# esp32car.net
KiCad netlist of a schematic drawn in EasyEDA Pro
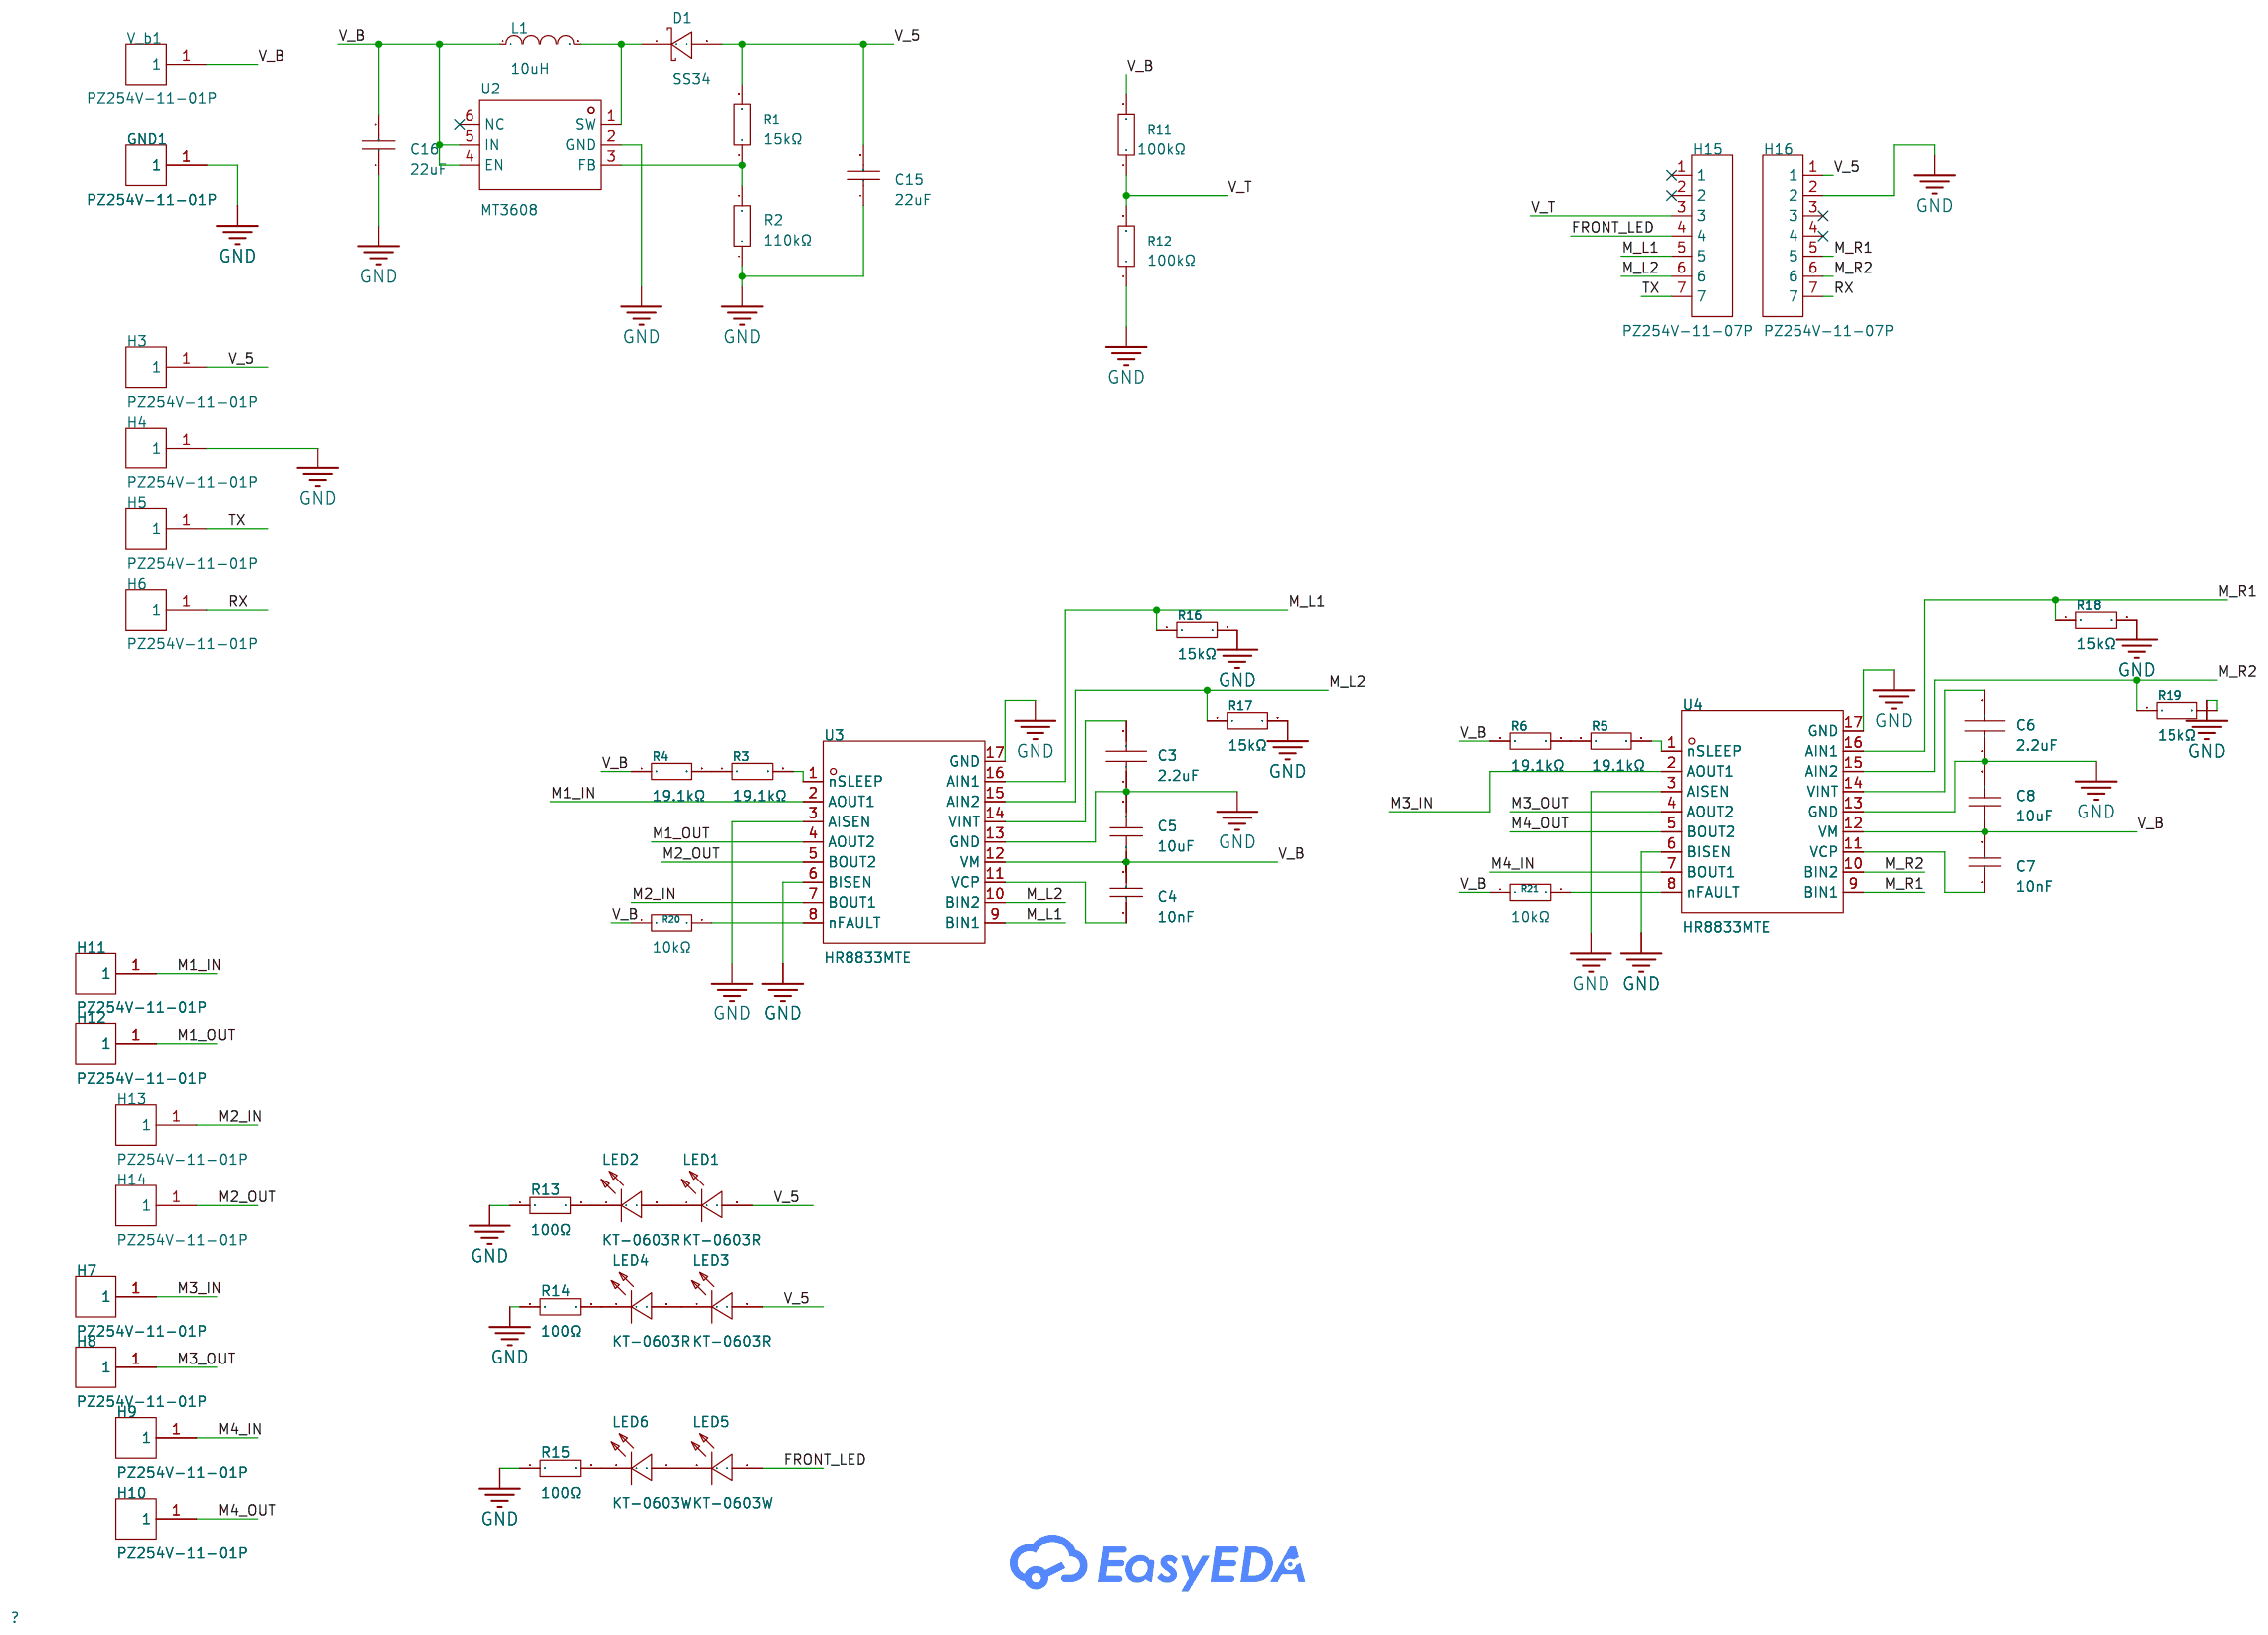
[diagram p0: schematic sheet]

(export (version "E")
  (design (tool "Eeschema 10.0.6"))
  (components
    (comp (ref "C3")
      (value "2.2uF")
      (footprint "easyedapro:C0402")
      (fields
        (field (name "Manufacturer Part") "CL05A225MQ5NSNC")
        (field (name "Manufacturer") "SAMSUNG(三星)")
      )
      (libsource (lib "easyedapro") (part "CL05A225MQ5NSNC"))
    )
    (comp (ref "C4")
      (value "10nF")
      (footprint "easyedapro:C0402")
      (fields
        (field (name "Manufacturer Part") "CL05B103KB5NNNC")
        (field (name "Manufacturer") "SAMSUNG(三星)")
      )
      (libsource (lib "easyedapro") (part "CL05B103KB5NNNC"))
    )
    (comp (ref "C5")
      (value "10uF")
      (footprint "easyedapro:C0603")
      (fields
        (field (name "Manufacturer Part") "CL10A106KP8NNNC")
        (field (name "Manufacturer") "SAMSUNG(三星)")
      )
      (libsource (lib "easyedapro") (part "CL10A106KP8NNNC"))
    )
    (comp (ref "C6")
      (value "2.2uF")
      (footprint "easyedapro:C0402")
      (fields
        (field (name "Manufacturer Part") "CL05A225MQ5NSNC")
        (field (name "Manufacturer") "SAMSUNG(三星)")
      )
      (libsource (lib "easyedapro") (part "CL05A225MQ5NSNC"))
    )
    (comp (ref "C7")
      (value "10nF")
      (footprint "easyedapro:C0402")
      (fields
        (field (name "Manufacturer Part") "CL05B103KB5NNNC")
        (field (name "Manufacturer") "SAMSUNG(三星)")
      )
      (libsource (lib "easyedapro") (part "CL05B103KB5NNNC"))
    )
    (comp (ref "C8")
      (value "10uF")
      (footprint "easyedapro:C0603")
      (fields
        (field (name "Manufacturer Part") "CL10A106KP8NNNC")
        (field (name "Manufacturer") "SAMSUNG(三星)")
      )
      (libsource (lib "easyedapro") (part "CL10A106KP8NNNC"))
    )
    (comp (ref "C15")
      (value "22uF")
      (footprint "easyedapro:C1206")
      (description "Capacitance:22uF Tolerance:±10% Tolerance:±10% Voltage Rating:10V Temperature Coefficient:X5R")
      (fields (field (name "Manufacturer Part") "1206X226K100NT") (field (name "Manufacturer") "FH(风华)"))
      (libsource (lib "easyedapro") (part "1206X226K100NT"))
    )
    (comp (ref "C16")
      (value "22uF")
      (footprint "easyedapro:C1206")
      (description "Capacitance:22uF Tolerance:±10% Tolerance:±10% Voltage Rating:10V Temperature Coefficient:X5R")
      (fields (field (name "Manufacturer Part") "1206X226K100NT") (field (name "Manufacturer") "FH(风华)"))
      (libsource (lib "easyedapro") (part "1206X226K100NT"))
    )
    (comp (ref "D1")
      (value "SS34")
      (footprint "easyedapro:SMA_L4.3-W2.6-LS5.2-RD")
      (fields (field (name "Manufacturer") "MDD(辰达半导体)"))
      (libsource (lib "easyedapro") (part "SS34_C8678"))
    )
    (comp (ref "GND1")
      (value "PZ254V-11-01P")
      (footprint "easyedapro:HDR-TH_1P-P2.54-V-M")
      (fields (field (name "Manufacturer") "XFCN(兴飞)"))
      (libsource (lib "easyedapro") (part "PZ254V-11-01P"))
    )
    (comp (ref "H3")
      (value "PZ254V-11-01P")
      (footprint "easyedapro:HDR-TH_1P-P2.54-V-M")
      (fields (field (name "Manufacturer") "XFCN(兴飞)"))
      (libsource (lib "easyedapro") (part "PZ254V-11-01P"))
    )
    (comp (ref "H4")
      (value "PZ254V-11-01P")
      (footprint "easyedapro:HDR-TH_1P-P2.54-V-M")
      (fields (field (name "Manufacturer") "XFCN(兴飞)"))
      (libsource (lib "easyedapro") (part "PZ254V-11-01P"))
    )
    (comp (ref "H5")
      (value "PZ254V-11-01P")
      (footprint "easyedapro:HDR-TH_1P-P2.54-V-M")
      (fields (field (name "Manufacturer") "XFCN(兴飞)"))
      (libsource (lib "easyedapro") (part "PZ254V-11-01P"))
    )
    (comp (ref "H6")
      (value "PZ254V-11-01P")
      (footprint "easyedapro:HDR-TH_1P-P2.54-V-M")
      (fields (field (name "Manufacturer") "XFCN(兴飞)"))
      (libsource (lib "easyedapro") (part "PZ254V-11-01P"))
    )
    (comp (ref "H7")
      (value "PZ254V-11-01P")
      (footprint "easyedapro:HDR-TH_1P-P2.54-V-M")
      (fields (field (name "Manufacturer") "XFCN(兴飞)"))
      (libsource (lib "easyedapro") (part "PZ254V-11-01P"))
    )
    (comp (ref "H8")
      (value "PZ254V-11-01P")
      (footprint "easyedapro:HDR-TH_1P-P2.54-V-M")
      (fields (field (name "Manufacturer") "XFCN(兴飞)"))
      (libsource (lib "easyedapro") (part "PZ254V-11-01P"))
    )
    (comp (ref "H9")
      (value "PZ254V-11-01P")
      (footprint "easyedapro:HDR-TH_1P-P2.54-V-M")
      (fields (field (name "Manufacturer") "XFCN(兴飞)"))
      (libsource (lib "easyedapro") (part "PZ254V-11-01P"))
    )
    (comp (ref "H10")
      (value "PZ254V-11-01P")
      (footprint "easyedapro:HDR-TH_1P-P2.54-V-M")
      (fields (field (name "Manufacturer") "XFCN(兴飞)"))
      (libsource (lib "easyedapro") (part "PZ254V-11-01P"))
    )
    (comp (ref "H11")
      (value "PZ254V-11-01P")
      (footprint "easyedapro:HDR-TH_1P-P2.54-V-M")
      (fields (field (name "Manufacturer") "XFCN(兴飞)"))
      (libsource (lib "easyedapro") (part "PZ254V-11-01P"))
    )
    (comp (ref "H12")
      (value "PZ254V-11-01P")
      (footprint "easyedapro:HDR-TH_1P-P2.54-V-M")
      (fields (field (name "Manufacturer") "XFCN(兴飞)"))
      (libsource (lib "easyedapro") (part "PZ254V-11-01P"))
    )
    (comp (ref "H13")
      (value "PZ254V-11-01P")
      (footprint "easyedapro:HDR-TH_1P-P2.54-V-M")
      (fields (field (name "Manufacturer") "XFCN(兴飞)"))
      (libsource (lib "easyedapro") (part "PZ254V-11-01P"))
    )
    (comp (ref "H14")
      (value "PZ254V-11-01P")
      (footprint "easyedapro:HDR-TH_1P-P2.54-V-M")
      (fields (field (name "Manufacturer") "XFCN(兴飞)"))
      (libsource (lib "easyedapro") (part "PZ254V-11-01P"))
    )
    (comp (ref "H15")
      (value "PZ254V-11-07P")
      (footprint "easyedapro:HDR-TH_7P-P2.54-V-M")
      (fields (field (name "Manufacturer") "XFCN(兴飞)"))
      (libsource (lib "easyedapro") (part "PZ254V-11-07P"))
    )
    (comp (ref "H16")
      (value "PZ254V-11-07P")
      (footprint "easyedapro:HDR-TH_7P-P2.54-V-M")
      (fields (field (name "Manufacturer") "XFCN(兴飞)"))
      (libsource (lib "easyedapro") (part "PZ254V-11-07P"))
    )
    (comp (ref "L1")
      (value "10uH")
      (footprint "easyedapro:L1008")
      (fields (field (name "Manufacturer Part") "MLP2520S100MT0S1") (field (name "Manufacturer") "TDK"))
      (libsource (lib "easyedapro") (part "MLP2520S100MT0S1"))
    )
    (comp (ref "LED1")
      (value "KT-0603R")
      (footprint "easyedapro:LED0603-RD")
      (fields (field (name "Manufacturer") "KENTO"))
      (libsource (lib "easyedapro") (part "KT-0603R"))
    )
    (comp (ref "LED2")
      (value "KT-0603R")
      (footprint "easyedapro:LED0603-RD")
      (fields (field (name "Manufacturer") "KENTO"))
      (libsource (lib "easyedapro") (part "KT-0603R"))
    )
    (comp (ref "LED3")
      (value "KT-0603R")
      (footprint "easyedapro:LED0603-RD")
      (fields (field (name "Manufacturer") "KENTO"))
      (libsource (lib "easyedapro") (part "KT-0603R"))
    )
    (comp (ref "LED4")
      (value "KT-0603R")
      (footprint "easyedapro:LED0603-RD")
      (fields (field (name "Manufacturer") "KENTO"))
      (libsource (lib "easyedapro") (part "KT-0603R"))
    )
    (comp (ref "LED5")
      (value "KT-0603W")
      (footprint "easyedapro:LED0603-R-RD_WHITE")
      (description "Emitted Color:White")
      (fields (field (name "Manufacturer") "KENTO"))
      (libsource (lib "easyedapro") (part "0603White light_C2290"))
    )
    (comp (ref "LED6")
      (value "KT-0603W")
      (footprint "easyedapro:LED0603-R-RD_WHITE")
      (description "Emitted Color:White")
      (fields (field (name "Manufacturer") "KENTO"))
      (libsource (lib "easyedapro") (part "0603White light_C2290"))
    )
    (comp (ref "R1")
      (value "15kΩ")
      (footprint "easyedapro:R0402")
      (fields
        (field (name "Manufacturer Part") "0402WGF1502TCE")
        (field (name "Manufacturer") "UNI-ROYAL(厚声)")
      )
      (libsource (lib "easyedapro") (part "0402WGF1502TCE"))
    )
    (comp (ref "R2")
      (value "110kΩ")
      (footprint "easyedapro:R0603")
      (fields
        (field (name "Manufacturer Part") "0603WAF1103T5E")
        (field (name "Manufacturer") "UNI-ROYAL(厚声)")
      )
      (libsource (lib "easyedapro") (part "0603WAF1103T5E"))
    )
    (comp (ref "R3")
      (value "19.1kΩ")
      (footprint "easyedapro:R0402")
      (fields
        (field (name "Manufacturer Part") "0402WGF1912TCE")
        (field (name "Manufacturer") "UNI-ROYAL(厚声)")
      )
      (libsource (lib "easyedapro") (part "0402WGF1912TCE"))
    )
    (comp (ref "R4")
      (value "19.1kΩ")
      (footprint "easyedapro:R0402")
      (fields
        (field (name "Manufacturer Part") "0402WGF1912TCE")
        (field (name "Manufacturer") "UNI-ROYAL(厚声)")
      )
      (libsource (lib "easyedapro") (part "0402WGF1912TCE"))
    )
    (comp (ref "R5")
      (value "19.1kΩ")
      (footprint "easyedapro:R0402")
      (fields
        (field (name "Manufacturer Part") "0402WGF1912TCE")
        (field (name "Manufacturer") "UNI-ROYAL(厚声)")
      )
      (libsource (lib "easyedapro") (part "0402WGF1912TCE"))
    )
    (comp (ref "R6")
      (value "19.1kΩ")
      (footprint "easyedapro:R0402")
      (fields
        (field (name "Manufacturer Part") "0402WGF1912TCE")
        (field (name "Manufacturer") "UNI-ROYAL(厚声)")
      )
      (libsource (lib "easyedapro") (part "0402WGF1912TCE"))
    )
    (comp (ref "R11")
      (value "100kΩ")
      (footprint "easyedapro:R0402")
      (fields
        (field (name "Manufacturer Part") "0402WGF1003TCE")
        (field (name "Manufacturer") "UNI-ROYAL(厚声)")
      )
      (libsource (lib "easyedapro") (part "0402WGF1003TCE"))
    )
    (comp (ref "R12")
      (value "100kΩ")
      (footprint "easyedapro:R0402")
      (fields
        (field (name "Manufacturer Part") "0402WGF1003TCE")
        (field (name "Manufacturer") "UNI-ROYAL(厚声)")
      )
      (libsource (lib "easyedapro") (part "0402WGF1003TCE"))
    )
    (comp (ref "R13")
      (value "100Ω")
      (footprint "easyedapro:R0402")
      (fields
        (field (name "Manufacturer Part") "0402WGF1000TCE")
        (field (name "Manufacturer") "UNI-ROYAL(厚声)")
      )
      (libsource (lib "easyedapro") (part "0402WGF1000TCE"))
    )
    (comp (ref "R14")
      (value "100Ω")
      (footprint "easyedapro:R0402")
      (fields
        (field (name "Manufacturer Part") "0402WGF1000TCE")
        (field (name "Manufacturer") "UNI-ROYAL(厚声)")
      )
      (libsource (lib "easyedapro") (part "0402WGF1000TCE"))
    )
    (comp (ref "R15")
      (value "100Ω")
      (footprint "easyedapro:R0402")
      (fields
        (field (name "Manufacturer Part") "0402WGF1000TCE")
        (field (name "Manufacturer") "UNI-ROYAL(厚声)")
      )
      (libsource (lib "easyedapro") (part "0402WGF1000TCE"))
    )
    (comp (ref "R16")
      (value "15kΩ")
      (footprint "easyedapro:R0402")
      (fields
        (field (name "Manufacturer Part") "0402WGF1502TCE")
        (field (name "Manufacturer") "UNI-ROYAL(厚声)")
      )
      (libsource (lib "easyedapro") (part "0402WGF1502TCE"))
    )
    (comp (ref "R17")
      (value "15kΩ")
      (footprint "easyedapro:R0402")
      (fields
        (field (name "Manufacturer Part") "0402WGF1502TCE")
        (field (name "Manufacturer") "UNI-ROYAL(厚声)")
      )
      (libsource (lib "easyedapro") (part "0402WGF1502TCE"))
    )
    (comp (ref "R18")
      (value "15kΩ")
      (footprint "easyedapro:R0402")
      (fields
        (field (name "Manufacturer Part") "0402WGF1502TCE")
        (field (name "Manufacturer") "UNI-ROYAL(厚声)")
      )
      (libsource (lib "easyedapro") (part "0402WGF1502TCE"))
    )
    (comp (ref "R19")
      (value "15kΩ")
      (footprint "easyedapro:R0402")
      (fields
        (field (name "Manufacturer Part") "0402WGF1502TCE")
        (field (name "Manufacturer") "UNI-ROYAL(厚声)")
      )
      (libsource (lib "easyedapro") (part "0402WGF1502TCE"))
    )
    (comp (ref "R20")
      (value "10kΩ")
      (footprint "easyedapro:R0603")
      (fields
        (field (name "Manufacturer Part") "0603WAF1002T5E")
        (field (name "Manufacturer") "UNI-ROYAL(厚声)")
      )
      (libsource (lib "easyedapro") (part "0603WAF1002T5E"))
    )
    (comp (ref "R21")
      (value "10kΩ")
      (footprint "easyedapro:R0603")
      (fields
        (field (name "Manufacturer Part") "0603WAF1002T5E")
        (field (name "Manufacturer") "UNI-ROYAL(厚声)")
      )
      (libsource (lib "easyedapro") (part "0603WAF1002T5E"))
    )
    (comp (ref "U2")
      (value "MT3608")
      (footprint "easyedapro:SOT-23-6_L2.9-W1.6-P0.95-LS2.8-BL")
      (fields (field (name "Manufacturer") "西安航天民芯"))
      (libsource (lib "easyedapro") (part "MT3608"))
    )
    (comp (ref "U3")
      (value "HR8833MTE")
      (footprint "easyedapro:TSSOP-16_L5.0-W4.4-P0.65-LS6.4-BL-EP3.0")
      (fields (field (name "Manufacturer") "嘉兴禾润"))
      (libsource (lib "easyedapro") (part "HR8833MTE"))
    )
    (comp (ref "U4")
      (value "HR8833MTE")
      (footprint "easyedapro:TSSOP-16_L5.0-W4.4-P0.65-LS6.4-BL-EP3.0")
      (fields (field (name "Manufacturer") "嘉兴禾润"))
      (libsource (lib "easyedapro") (part "HR8833MTE"))
    )
    (comp (ref "V_b1")
      (value "PZ254V-11-01P")
      (footprint "easyedapro:HDR-TH_1P-P2.54-V-M")
      (fields (field (name "Manufacturer") "XFCN(兴飞)"))
      (libsource (lib "easyedapro") (part "PZ254V-11-01P"))
    )
  )
  (nets
    (net (code "1") (name "/FRONT_LED") (class "Default")
      (node (ref "H15") (pin "4") (pinfunction "4_4") (pintype "unspecified"))
      (node (ref "LED5") (pin "1") (pinfunction "A_1") (pintype "unspecified"))
    )
    (net (code "2") (name "/M1_IN") (class "Default")
      (node (ref "H11") (pin "1") (pinfunction "1_1") (pintype "unspecified"))
      (node (ref "U3") (pin "2") (pinfunction "AOUT1_2") (pintype "unspecified"))
    )
    (net (code "3") (name "/M1_OUT") (class "Default")
      (node (ref "H12") (pin "1") (pinfunction "1_1") (pintype "unspecified"))
      (node (ref "U3") (pin "4") (pinfunction "AOUT2_4") (pintype "unspecified"))
    )
    (net (code "4") (name "/M2_IN") (class "Default")
      (node (ref "H13") (pin "1") (pinfunction "1_1") (pintype "unspecified"))
      (node (ref "U3") (pin "7") (pinfunction "BOUT1_7") (pintype "unspecified"))
    )
    (net (code "5") (name "/M2_OUT") (class "Default")
      (node (ref "H14") (pin "1") (pinfunction "1_1") (pintype "unspecified"))
      (node (ref "U3") (pin "5") (pinfunction "BOUT2_5") (pintype "unspecified"))
    )
    (net (code "6") (name "/M3_IN") (class "Default")
      (node (ref "H7") (pin "1") (pinfunction "1_1") (pintype "unspecified"))
      (node (ref "U4") (pin "2") (pinfunction "AOUT1_2") (pintype "unspecified"))
    )
    (net (code "7") (name "/M3_OUT") (class "Default")
      (node (ref "H8") (pin "1") (pinfunction "1_1") (pintype "unspecified"))
      (node (ref "U4") (pin "4") (pinfunction "AOUT2_4") (pintype "unspecified"))
    )
    (net (code "8") (name "/M4_IN") (class "Default")
      (node (ref "H9") (pin "1") (pinfunction "1_1") (pintype "unspecified"))
      (node (ref "U4") (pin "7") (pinfunction "BOUT1_7") (pintype "unspecified"))
    )
    (net (code "9") (name "/M4_OUT") (class "Default")
      (node (ref "H10") (pin "1") (pinfunction "1_1") (pintype "unspecified"))
      (node (ref "U4") (pin "5") (pinfunction "BOUT2_5") (pintype "unspecified"))
    )
    (net (code "10") (name "/M_L1") (class "Default")
      (node (ref "H15") (pin "5") (pinfunction "5_5") (pintype "unspecified"))
      (node (ref "R16") (pin "1") (pinfunction "1_1") (pintype "input"))
      (node (ref "U3") (pin "16") (pinfunction "AIN1_16") (pintype "unspecified"))
      (node (ref "U3") (pin "9") (pinfunction "BIN1_9") (pintype "unspecified"))
    )
    (net (code "11") (name "/M_L2") (class "Default")
      (node (ref "H15") (pin "6") (pinfunction "6_6") (pintype "unspecified"))
      (node (ref "R17") (pin "1") (pinfunction "1_1") (pintype "input"))
      (node (ref "U3") (pin "10") (pinfunction "BIN2_10") (pintype "unspecified"))
      (node (ref "U3") (pin "15") (pinfunction "AIN2_15") (pintype "unspecified"))
    )
    (net (code "12") (name "/M_R1") (class "Default")
      (node (ref "H16") (pin "5") (pinfunction "5_5") (pintype "unspecified"))
      (node (ref "R18") (pin "1") (pinfunction "1_1") (pintype "input"))
      (node (ref "U4") (pin "16") (pinfunction "AIN1_16") (pintype "unspecified"))
      (node (ref "U4") (pin "9") (pinfunction "BIN1_9") (pintype "unspecified"))
    )
    (net (code "13") (name "/M_R2") (class "Default")
      (node (ref "H16") (pin "6") (pinfunction "6_6") (pintype "unspecified"))
      (node (ref "R19") (pin "1") (pinfunction "1_1") (pintype "input"))
      (node (ref "U4") (pin "10") (pinfunction "BIN2_10") (pintype "unspecified"))
      (node (ref "U4") (pin "15") (pinfunction "AIN2_15") (pintype "unspecified"))
    )
    (net (code "14") (name "/RX") (class "Default")
      (node (ref "H16") (pin "7") (pinfunction "7_7") (pintype "unspecified"))
      (node (ref "H6") (pin "1") (pinfunction "1_1") (pintype "unspecified"))
    )
    (net (code "15") (name "/TX") (class "Default")
      (node (ref "H15") (pin "7") (pinfunction "7_7") (pintype "unspecified"))
      (node (ref "H5") (pin "1") (pinfunction "1_1") (pintype "unspecified"))
    )
    (net (code "16") (name "/V_5") (class "Default")
      (node (ref "C15") (pin "2") (pinfunction "2_2") (pintype "input"))
      (node (ref "D1") (pin "2") (pinfunction "A_2") (pintype "unspecified"))
      (node (ref "H16") (pin "1") (pinfunction "1_1") (pintype "unspecified"))
      (node (ref "H3") (pin "1") (pinfunction "1_1") (pintype "unspecified"))
      (node (ref "LED1") (pin "2") (pinfunction "A_2") (pintype "unspecified"))
      (node (ref "LED3") (pin "2") (pinfunction "A_2") (pintype "unspecified"))
      (node (ref "R1") (pin "2") (pinfunction "2_2") (pintype "input"))
    )
    (net (code "17") (name "/V_B") (class "Default")
      (node (ref "C16") (pin "2") (pinfunction "2_2") (pintype "input"))
      (node (ref "C4") (pin "2") (pinfunction "2_2") (pintype "input"))
      (node (ref "C5") (pin "1") (pinfunction "1_1") (pintype "unspecified"))
      (node (ref "C7") (pin "2") (pinfunction "2_2") (pintype "input"))
      (node (ref "C8") (pin "1") (pinfunction "1_1") (pintype "unspecified"))
      (node (ref "L1") (pin "1") (pinfunction "1_1") (pintype "unspecified"))
      (node (ref "R11") (pin "2") (pinfunction "2_2") (pintype "input"))
      (node (ref "R20") (pin "1") (pinfunction "1_1") (pintype "input"))
      (node (ref "R21") (pin "1") (pinfunction "1_1") (pintype "input"))
      (node (ref "R4") (pin "1") (pinfunction "1_1") (pintype "input"))
      (node (ref "R6") (pin "1") (pinfunction "1_1") (pintype "input"))
      (node (ref "U2") (pin "4") (pinfunction "EN_4") (pintype "unspecified"))
      (node (ref "U2") (pin "5") (pinfunction "IN_5") (pintype "unspecified"))
      (node (ref "U3") (pin "12") (pinfunction "VM_12") (pintype "unspecified"))
      (node (ref "U4") (pin "12") (pinfunction "VM_12") (pintype "unspecified"))
      (node (ref "V_b1") (pin "1") (pinfunction "1_1") (pintype "unspecified"))
    )
    (net (code "18") (name "/V_T") (class "Default")
      (node (ref "H15") (pin "3") (pinfunction "3_3") (pintype "unspecified"))
      (node (ref "R11") (pin "1") (pinfunction "1_1") (pintype "input"))
      (node (ref "R12") (pin "2") (pinfunction "2_2") (pintype "input"))
    )
    (net (code "19") (name "GND") (class "Default")
      (node (ref "C15") (pin "1") (pinfunction "1_1") (pintype "input"))
      (node (ref "C16") (pin "1") (pinfunction "1_1") (pintype "input"))
      (node (ref "C3") (pin "1") (pinfunction "1_1") (pintype "unspecified"))
      (node (ref "C5") (pin "2") (pinfunction "2_2") (pintype "unspecified"))
      (node (ref "C6") (pin "1") (pinfunction "1_1") (pintype "unspecified"))
      (node (ref "C8") (pin "2") (pinfunction "2_2") (pintype "unspecified"))
      (node (ref "GND1") (pin "1") (pinfunction "1_1") (pintype "unspecified"))
      (node (ref "H16") (pin "2") (pinfunction "2_2") (pintype "unspecified"))
      (node (ref "H4") (pin "1") (pinfunction "1_1") (pintype "unspecified"))
      (node (ref "R12") (pin "1") (pinfunction "1_1") (pintype "input"))
      (node (ref "R13") (pin "1") (pinfunction "1_1") (pintype "input"))
      (node (ref "R14") (pin "1") (pinfunction "1_1") (pintype "input"))
      (node (ref "R15") (pin "1") (pinfunction "1_1") (pintype "input"))
      (node (ref "R16") (pin "2") (pinfunction "2_2") (pintype "input"))
      (node (ref "R17") (pin "2") (pinfunction "2_2") (pintype "input"))
      (node (ref "R18") (pin "2") (pinfunction "2_2") (pintype "input"))
      (node (ref "R19") (pin "2") (pinfunction "2_2") (pintype "input"))
      (node (ref "R2") (pin "1") (pinfunction "1_1") (pintype "input"))
      (node (ref "U2") (pin "2") (pinfunction "GND_2") (pintype "unspecified"))
      (node (ref "U3") (pin "13") (pinfunction "GND_13") (pintype "unspecified"))
      (node (ref "U3") (pin "17") (pinfunction "GND_17") (pintype "unspecified"))
      (node (ref "U3") (pin "3") (pinfunction "AISEN_3") (pintype "unspecified"))
      (node (ref "U3") (pin "6") (pinfunction "BISEN_6") (pintype "unspecified"))
      (node (ref "U4") (pin "13") (pinfunction "GND_13") (pintype "unspecified"))
      (node (ref "U4") (pin "17") (pinfunction "GND_17") (pintype "unspecified"))
      (node (ref "U4") (pin "3") (pinfunction "AISEN_3") (pintype "unspecified"))
      (node (ref "U4") (pin "6") (pinfunction "BISEN_6") (pintype "unspecified"))
    )
    (net (code "20") (name "Net-(D1-K)") (class "Default")
      (node (ref "D1") (pin "1") (pinfunction "K_1") (pintype "unspecified"))
      (node (ref "L1") (pin "2") (pinfunction "2_2") (pintype "unspecified"))
      (node (ref "U2") (pin "1") (pinfunction "SW_1") (pintype "unspecified"))
    )
    (net (code "21") (name "Net-(LED1-K)") (class "Default")
      (node (ref "LED1") (pin "1") (pinfunction "K_1") (pintype "unspecified"))
      (node (ref "LED2") (pin "2") (pinfunction "A_2") (pintype "unspecified"))
    )
    (net (code "22") (name "Net-(LED2-K)") (class "Default")
      (node (ref "LED2") (pin "1") (pinfunction "K_1") (pintype "unspecified"))
      (node (ref "R13") (pin "2") (pinfunction "2_2") (pintype "input"))
    )
    (net (code "23") (name "Net-(LED3-K)") (class "Default")
      (node (ref "LED3") (pin "1") (pinfunction "K_1") (pintype "unspecified"))
      (node (ref "LED4") (pin "2") (pinfunction "A_2") (pintype "unspecified"))
    )
    (net (code "24") (name "Net-(LED4-K)") (class "Default")
      (node (ref "LED4") (pin "1") (pinfunction "K_1") (pintype "unspecified"))
      (node (ref "R14") (pin "2") (pinfunction "2_2") (pintype "input"))
    )
    (net (code "25") (name "Net-(LED5-K)") (class "Default")
      (node (ref "LED5") (pin "2") (pinfunction "K_2") (pintype "unspecified"))
      (node (ref "LED6") (pin "1") (pinfunction "A_1") (pintype "unspecified"))
    )
    (net (code "26") (name "Net-(LED6-K)") (class "Default")
      (node (ref "LED6") (pin "2") (pinfunction "K_2") (pintype "unspecified"))
      (node (ref "R15") (pin "2") (pinfunction "2_2") (pintype "input"))
    )
    (net (code "27") (name "Net-(R3-Pad1)") (class "Default")
      (node (ref "R3") (pin "1") (pinfunction "1_1") (pintype "input"))
      (node (ref "R4") (pin "2") (pinfunction "2_2") (pintype "input"))
    )
    (net (code "28") (name "Net-(R5-Pad1)") (class "Default")
      (node (ref "R5") (pin "1") (pinfunction "1_1") (pintype "input"))
      (node (ref "R6") (pin "2") (pinfunction "2_2") (pintype "input"))
    )
    (net (code "29") (name "Net-(U2-FB)") (class "Default")
      (node (ref "R1") (pin "1") (pinfunction "1_1") (pintype "input"))
      (node (ref "R2") (pin "2") (pinfunction "2_2") (pintype "input"))
      (node (ref "U2") (pin "3") (pinfunction "FB_3") (pintype "unspecified"))
    )
    (net (code "30") (name "Net-(U3-VCP)") (class "Default")
      (node (ref "C4") (pin "1") (pinfunction "1_1") (pintype "input"))
      (node (ref "U3") (pin "11") (pinfunction "VCP_11") (pintype "unspecified"))
    )
    (net (code "31") (name "Net-(U3-VINT)") (class "Default")
      (node (ref "C3") (pin "2") (pinfunction "2_2") (pintype "unspecified"))
      (node (ref "U3") (pin "14") (pinfunction "VINT_14") (pintype "unspecified"))
    )
    (net (code "32") (name "Net-(U3-nFAULT)") (class "Default")
      (node (ref "R20") (pin "2") (pinfunction "2_2") (pintype "input"))
      (node (ref "U3") (pin "8") (pinfunction "nFAULT_8") (pintype "unspecified"))
    )
    (net (code "33") (name "Net-(U3-nSLEEP)") (class "Default")
      (node (ref "R3") (pin "2") (pinfunction "2_2") (pintype "input"))
      (node (ref "U3") (pin "1") (pinfunction "nSLEEP_1") (pintype "unspecified"))
    )
    (net (code "34") (name "Net-(U4-VCP)") (class "Default")
      (node (ref "C7") (pin "1") (pinfunction "1_1") (pintype "input"))
      (node (ref "U4") (pin "11") (pinfunction "VCP_11") (pintype "unspecified"))
    )
    (net (code "35") (name "Net-(U4-VINT)") (class "Default")
      (node (ref "C6") (pin "2") (pinfunction "2_2") (pintype "unspecified"))
      (node (ref "U4") (pin "14") (pinfunction "VINT_14") (pintype "unspecified"))
    )
    (net (code "36") (name "Net-(U4-nFAULT)") (class "Default")
      (node (ref "R21") (pin "2") (pinfunction "2_2") (pintype "input"))
      (node (ref "U4") (pin "8") (pinfunction "nFAULT_8") (pintype "unspecified"))
    )
    (net (code "37") (name "Net-(U4-nSLEEP)") (class "Default")
      (node (ref "R5") (pin "2") (pinfunction "2_2") (pintype "input"))
      (node (ref "U4") (pin "1") (pinfunction "nSLEEP_1") (pintype "unspecified"))
    )
    (net (code "38") (name "unconnected-(H15-Pad1)") (class "Default")
      (node (ref "H15") (pin "1") (pinfunction "1_1") (pintype "unspecified+no_connect"))
    )
    (net (code "39") (name "unconnected-(H15-Pad2)") (class "Default")
      (node (ref "H15") (pin "2") (pinfunction "2_2") (pintype "unspecified+no_connect"))
    )
    (net (code "40") (name "unconnected-(H16-Pad3)") (class "Default")
      (node (ref "H16") (pin "3") (pinfunction "3_3") (pintype "unspecified+no_connect"))
    )
    (net (code "41") (name "unconnected-(H16-Pad4)") (class "Default")
      (node (ref "H16") (pin "4") (pinfunction "4_4") (pintype "unspecified+no_connect"))
    )
    (net (code "42") (name "unconnected-(U2-NC-Pad6)") (class "Default")
      (node (ref "U2") (pin "6") (pinfunction "NC_6") (pintype "unspecified+no_connect"))
    )
  )
)
